# Focus_V7.net
KiCad netlist of a schematic drawn in EAGLE
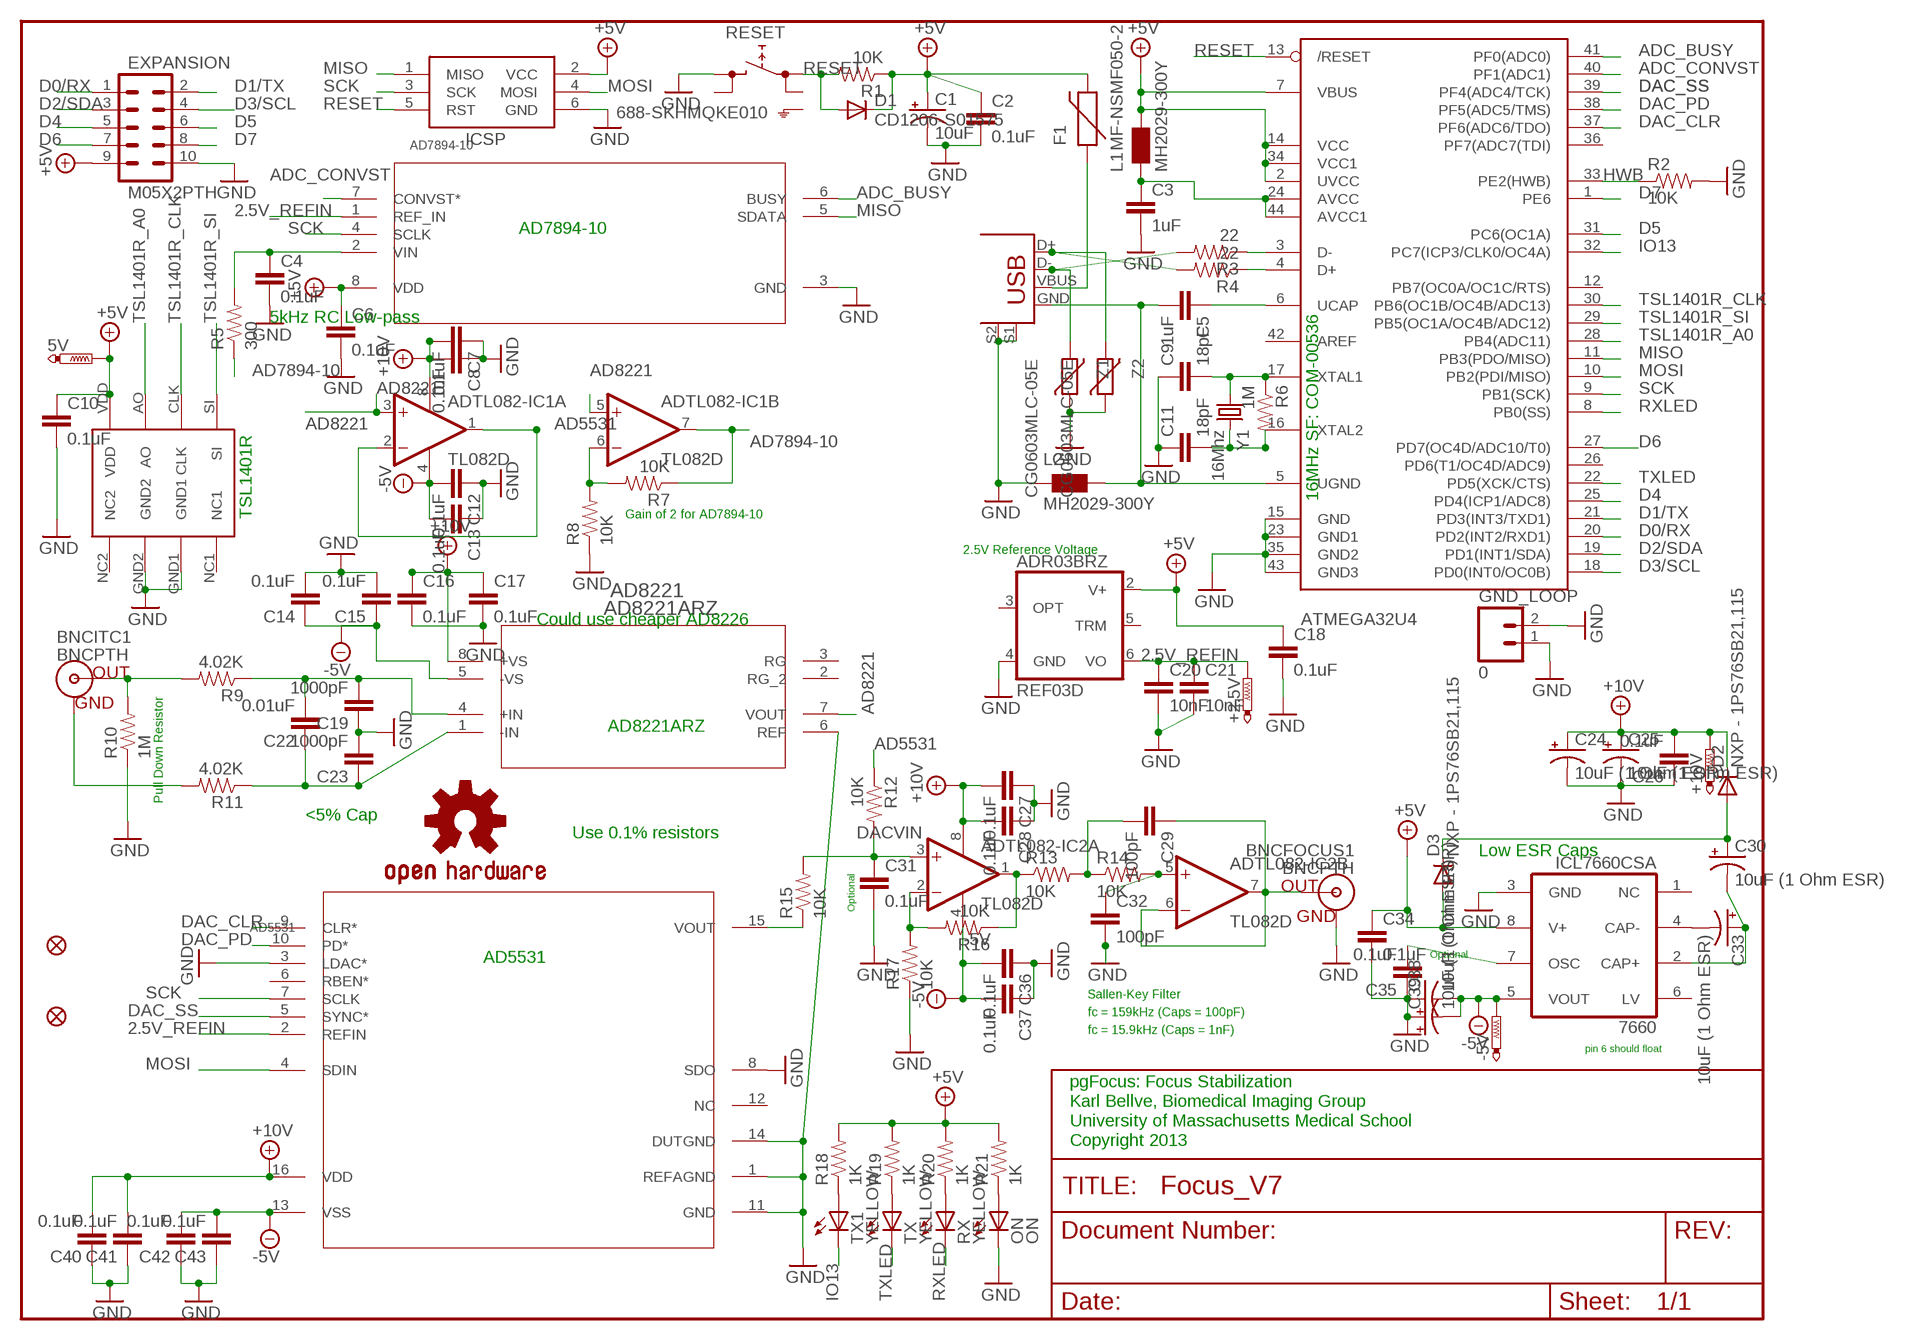
[diagram p0: schematic, sheet 1]

(export (version "E")
  (design (tool "Eeschema 10.0.6"))
  (components
    (comp (ref "+2.5V")
      (value "PTR1TP20R")
      (footprint "eagle-import:TP20R")
      (libsource (lib "eagle-import") (part "PTR1TP20R"))
    )
    (comp (ref "+10V")
      (value "PTR1TP20R")
      (footprint "eagle-import:TP20R")
      (libsource (lib "eagle-import") (part "PTR1TP20R"))
    )
    (comp (ref "-5V")
      (value "PTR1TP20R")
      (footprint "eagle-import:TP20R")
      (libsource (lib "eagle-import") (part "PTR1TP20R"))
    )
    (comp (ref "5V")
      (value "PTR1TP20R")
      (footprint "eagle-import:TP20R")
      (libsource (lib "eagle-import") (part "PTR1TP20R"))
    )
    (comp (ref "7660")
      (value "ICL7660CSA")
      (footprint "eagle-import:SO08")
      (fields (field (name "MF") "MAXIM"))
      (libsource (lib "eagle-import") (part "ICL7660CSA"))
    )
    (comp (ref "AD5531")
      (value "AD5531BRUZ")
      (footprint "eagle-import:RU_16")
      (libsource (lib "eagle-import") (part "AD5531BRUZ"))
    )
    (comp (ref "AD7894-10")
      (value "AD7894ARZ-10")
      (footprint "eagle-import:R_8")
      (fields (field (name "MANUFACTURER_PART_NUMBER") "AD7894ARZ-3"))
      (libsource (lib "eagle-import") (part "AD7894ARZ-3"))
    )
    (comp (ref "AD8221")
      (value "AD8221ARZ")
      (footprint "eagle-import:R_8")
      (libsource (lib "eagle-import") (part "AD8221ARZ"))
    )
    (comp (ref "ADR03BRZ")
      (value "REF03D")
      (footprint "eagle-import:SO08")
      (libsource (lib "eagle-import") (part "REF03D"))
    )
    (comp (ref "ADTL082-IC1")
      (value "TL082D")
      (footprint "eagle-import:SO08")
      (libsource (lib "eagle-import") (part "TL082D"))
    )
    (comp (ref "ADTL082-IC2")
      (value "TL082D")
      (footprint "eagle-import:SO08")
      (libsource (lib "eagle-import") (part "TL082D"))
    )
    (comp (ref "ATMEGA32U4")
      (value "ATMEGA32U4-AU")
      (footprint "eagle-import:TQFP44")
      (libsource (lib "eagle-import") (part "ATMEGA32U4-AU"))
    )
    (comp (ref "BNCFOCUS1")
      (value "BNCPTH")
      (footprint "eagle-import:BNC")
      (libsource (lib "eagle-import") (part "BNCPTH"))
    )
    (comp (ref "BNCITC1")
      (value "BNCPTH")
      (footprint "eagle-import:BNC")
      (libsource (lib "eagle-import") (part "BNCPTH"))
    )
    (comp (ref "C1")
      (value "10uF")
      (footprint "eagle-import:EIA3216-KIT")
      (libsource (lib "eagle-import") (part "CAP_POL1206-KIT"))
    )
    (comp (ref "C2")
      (value "0.1uF")
      (footprint "eagle-import:0603-CAP")
      (libsource (lib "eagle-import") (part "CAP0603-CAP"))
    )
    (comp (ref "C3")
      (value "1uF")
      (footprint "eagle-import:0603-CAP")
      (libsource (lib "eagle-import") (part "CAP0603-CAP"))
    )
    (comp (ref "C4")
      (value "0.1uF")
      (footprint "eagle-import:0603-CAP")
      (libsource (lib "eagle-import") (part "CAP0603-CAP"))
    )
    (comp (ref "C5")
      (value "1uF")
      (footprint "eagle-import:0603-CAP")
      (libsource (lib "eagle-import") (part "CAP0603-CAP"))
    )
    (comp (ref "C6")
      (value "0.1uF")
      (footprint "eagle-import:0603-CAP")
      (libsource (lib "eagle-import") (part "CAP0603-CAP"))
    )
    (comp (ref "C7")
      (value "0.1uF")
      (footprint "eagle-import:0603-CAP")
      (libsource (lib "eagle-import") (part "CAP0603-CAP"))
    )
    (comp (ref "C8")
      (value "0.1uF")
      (footprint "eagle-import:0603-CAP")
      (libsource (lib "eagle-import") (part "CAP0603-CAP"))
    )
    (comp (ref "C9")
      (value "18pF")
      (footprint "eagle-import:0603-CAP")
      (libsource (lib "eagle-import") (part "CAP0603-CAP"))
    )
    (comp (ref "C10")
      (value "0.1uF")
      (footprint "eagle-import:0603-CAP")
      (libsource (lib "eagle-import") (part "CAP0603-CAP"))
    )
    (comp (ref "C11")
      (value "18pF")
      (footprint "eagle-import:0603-CAP")
      (libsource (lib "eagle-import") (part "CAP0603-CAP"))
    )
    (comp (ref "C12")
      (value "0.1uF")
      (footprint "eagle-import:0603-CAP")
      (libsource (lib "eagle-import") (part "CAP0603-CAP"))
    )
    (comp (ref "C13")
      (value "0.1uF")
      (footprint "eagle-import:0603-CAP")
      (libsource (lib "eagle-import") (part "CAP0603-CAP"))
    )
    (comp (ref "C14")
      (value "0.1uF")
      (footprint "eagle-import:0603-CAP")
      (libsource (lib "eagle-import") (part "CAP0603-CAP"))
    )
    (comp (ref "C15")
      (value "0.1uF")
      (footprint "eagle-import:0603-CAP")
      (libsource (lib "eagle-import") (part "CAP0603-CAP"))
    )
    (comp (ref "C16")
      (value "0.1uF")
      (footprint "eagle-import:0603-CAP")
      (libsource (lib "eagle-import") (part "CAP0603-CAP"))
    )
    (comp (ref "C17")
      (value "0.1uF")
      (footprint "eagle-import:0603-CAP")
      (libsource (lib "eagle-import") (part "CAP0603-CAP"))
    )
    (comp (ref "C18")
      (value "0.1uF")
      (footprint "eagle-import:0603-CAP")
      (libsource (lib "eagle-import") (part "CAP0603-CAP"))
    )
    (comp (ref "C19")
      (value "1000pF")
      (footprint "eagle-import:0603-CAP")
      (libsource (lib "eagle-import") (part "CAP0603-CAP"))
    )
    (comp (ref "C20")
      (value "10nF")
      (footprint "eagle-import:0603-CAP")
      (libsource (lib "eagle-import") (part "CAP0603-CAP"))
    )
    (comp (ref "C21")
      (value "10nF")
      (footprint "eagle-import:0603-CAP")
      (libsource (lib "eagle-import") (part "CAP0603-CAP"))
    )
    (comp (ref "C22")
      (value "0.01uF")
      (footprint "eagle-import:0603-CAP")
      (libsource (lib "eagle-import") (part "CAP0603-CAP"))
    )
    (comp (ref "C23")
      (value "1000pF")
      (footprint "eagle-import:0603-CAP")
      (libsource (lib "eagle-import") (part "CAP0603-CAP"))
    )
    (comp (ref "C24")
      (value "10uF (1 Ohm ESR)")
      (footprint "eagle-import:EIA3216-KIT")
      (libsource (lib "eagle-import") (part "CAP_POL1206-KIT"))
    )
    (comp (ref "C25")
      (value "10uF (1 Ohm ESR)")
      (footprint "eagle-import:EIA3216-KIT")
      (libsource (lib "eagle-import") (part "CAP_POL1206-KIT"))
    )
    (comp (ref "C26")
      (value "0.1uF")
      (footprint "eagle-import:0603-CAP")
      (libsource (lib "eagle-import") (part "CAP0603-CAP"))
    )
    (comp (ref "C27")
      (value "0.1uF")
      (footprint "eagle-import:0603-CAP")
      (libsource (lib "eagle-import") (part "CAP0603-CAP"))
    )
    (comp (ref "C28")
      (value "0.1uF")
      (footprint "eagle-import:0603-CAP")
      (libsource (lib "eagle-import") (part "CAP0603-CAP"))
    )
    (comp (ref "C29")
      (value "100pF")
      (footprint "eagle-import:0603-CAP")
      (libsource (lib "eagle-import") (part "CAP0603-CAP"))
    )
    (comp (ref "C30")
      (value "10uF (1 Ohm ESR)")
      (footprint "eagle-import:EIA3216-KIT")
      (libsource (lib "eagle-import") (part "CAP_POL1206-KIT"))
    )
    (comp (ref "C31")
      (value "0.1uF")
      (footprint "eagle-import:0603-CAP")
      (libsource (lib "eagle-import") (part "CAP0603-CAP"))
    )
    (comp (ref "C32")
      (value "100pF")
      (footprint "eagle-import:0603-CAP")
      (libsource (lib "eagle-import") (part "CAP0603-CAP"))
    )
    (comp (ref "C33")
      (value "10uF (1 Ohm ESR)")
      (footprint "eagle-import:EIA3216-KIT")
      (libsource (lib "eagle-import") (part "CAP_POL1206-KIT"))
    )
    (comp (ref "C34")
      (value "0.1uF")
      (footprint "eagle-import:0603-CAP")
      (libsource (lib "eagle-import") (part "CAP0603-CAP"))
    )
    (comp (ref "C35")
      (value "0.1uF")
      (footprint "eagle-import:0603-CAP")
      (libsource (lib "eagle-import") (part "CAP0603-CAP"))
    )
    (comp (ref "C36")
      (value "0.1uF")
      (footprint "eagle-import:0603-CAP")
      (libsource (lib "eagle-import") (part "CAP0603-CAP"))
    )
    (comp (ref "C37")
      (value "0.1uF")
      (footprint "eagle-import:0603-CAP")
      (libsource (lib "eagle-import") (part "CAP0603-CAP"))
    )
    (comp (ref "C38")
      (value "10uF (1 Ohm ESR)")
      (footprint "eagle-import:EIA3216-KIT")
      (libsource (lib "eagle-import") (part "CAP_POL1206-KIT"))
    )
    (comp (ref "C39")
      (value "10uF (1 Ohm ESR)")
      (footprint "eagle-import:EIA3216-KIT")
      (libsource (lib "eagle-import") (part "CAP_POL1206-KIT"))
    )
    (comp (ref "C40")
      (value "0.1uF")
      (footprint "eagle-import:0603-CAP")
      (libsource (lib "eagle-import") (part "CAP0603-CAP"))
    )
    (comp (ref "C41")
      (value "0.1uF")
      (footprint "eagle-import:0603-CAP")
      (libsource (lib "eagle-import") (part "CAP0603-CAP"))
    )
    (comp (ref "C42")
      (value "0.1uF")
      (footprint "eagle-import:0603-CAP")
      (libsource (lib "eagle-import") (part "CAP0603-CAP"))
    )
    (comp (ref "C43")
      (value "0.1uF")
      (footprint "eagle-import:0603-CAP")
      (libsource (lib "eagle-import") (part "CAP0603-CAP"))
    )
    (comp (ref "D1")
      (value "CD1206-S01575")
      (footprint "eagle-import:MINIMELF")
      (libsource (lib "eagle-import") (part "DIODE-MINIMELF"))
    )
    (comp (ref "D2")
      (value "NXP - 1PS76SB21,115")
      (footprint "eagle-import:SOD-323")
      (libsource (lib "eagle-import") (part "DIODESOD"))
    )
    (comp (ref "D3")
      (value "NXP - 1PS76SB21,115")
      (footprint "eagle-import:SOD-323")
      (libsource (lib "eagle-import") (part "DIODESOD"))
    )
    (comp (ref "EXPANSION")
      (value "M05X2PTH")
      (footprint "eagle-import:AVR_ICSP")
      (libsource (lib "eagle-import") (part "M05X2PTH"))
    )
    (comp (ref "F1")
      (value "MF-NSMF050-2")
      (footprint "eagle-import:PTC-1206")
      (libsource (lib "eagle-import") (part "PTCSMD"))
    )
    (comp (ref "GND_LOOP")
      (value "0")
      (footprint "eagle-import:1X02")
      (libsource (lib "eagle-import") (part "M02NG"))
    )
    (comp (ref "ICSP")
      (value "AVRISP-6")
      (footprint "eagle-import:AVRISP")
      (libsource (lib "eagle-import") (part "AVRISP-6"))
    )
    (comp (ref "JP1")
      (value "FIDUCIAL1.5X3")
      (footprint "eagle-import:FIDUCIAL-1.5X3")
      (libsource (lib "eagle-import") (part "FIDUCIAL1.5X3"))
    )
    (comp (ref "JP2")
      (value "FIDUCIAL1.5X3")
      (footprint "eagle-import:FIDUCIAL-1.5X3")
      (libsource (lib "eagle-import") (part "FIDUCIAL1.5X3"))
    )
    (comp (ref "L1")
      (value "MH2029-300Y")
      (footprint "eagle-import:0805")
      (libsource (lib "eagle-import") (part "WE-CBF_0805"))
    )
    (comp (ref "L2")
      (value "MH2029-300Y")
      (footprint "eagle-import:0805")
      (libsource (lib "eagle-import") (part "WE-CBF_0805"))
    )
    (comp (ref "ON")
      (value "ON")
      (footprint "eagle-import:CHIPLED_0805")
      (libsource (lib "eagle-import") (part "LEDCHIPLED_0805"))
    )
    (comp (ref "R1")
      (value "10K")
      (footprint "eagle-import:0603-RES")
      (libsource (lib "eagle-import") (part "RESISTOR0603-RES"))
    )
    (comp (ref "R2")
      (value "10K")
      (footprint "eagle-import:0603-RES")
      (libsource (lib "eagle-import") (part "RESISTOR0603-RES"))
    )
    (comp (ref "R3")
      (value "22")
      (footprint "eagle-import:0603-RES")
      (libsource (lib "eagle-import") (part "RESISTOR0603-RES"))
    )
    (comp (ref "R4")
      (value "22")
      (footprint "eagle-import:0603-RES")
      (libsource (lib "eagle-import") (part "RESISTOR0603-RES"))
    )
    (comp (ref "R5")
      (value "300")
      (footprint "eagle-import:0603-RES")
      (libsource (lib "eagle-import") (part "RESISTOR0603-RES"))
    )
    (comp (ref "R6")
      (value "1M")
      (footprint "eagle-import:0603-RES")
      (libsource (lib "eagle-import") (part "RESISTOR0603-RES"))
    )
    (comp (ref "R7")
      (value "10K")
      (footprint "eagle-import:0603-RES")
      (libsource (lib "eagle-import") (part "RESISTOR0603-RES"))
    )
    (comp (ref "R8")
      (value "10K")
      (footprint "eagle-import:0603-RES")
      (libsource (lib "eagle-import") (part "RESISTOR0603-RES"))
    )
    (comp (ref "R9")
      (value "4.02K")
      (footprint "eagle-import:0603-RES")
      (libsource (lib "eagle-import") (part "RESISTOR0603-RES"))
    )
    (comp (ref "R10")
      (value "1M")
      (footprint "eagle-import:0603-RES")
      (libsource (lib "eagle-import") (part "RESISTOR0603-RES"))
    )
    (comp (ref "R11")
      (value "4.02K")
      (footprint "eagle-import:0603-RES")
      (libsource (lib "eagle-import") (part "RESISTOR0603-RES"))
    )
    (comp (ref "R12")
      (value "10K")
      (footprint "eagle-import:0603-RES")
      (libsource (lib "eagle-import") (part "RESISTOR0603-RES"))
    )
    (comp (ref "R13")
      (value "10K")
      (footprint "eagle-import:0603-RES")
      (libsource (lib "eagle-import") (part "RESISTOR0603-RES"))
    )
    (comp (ref "R14")
      (value "10K")
      (footprint "eagle-import:0603-RES")
      (libsource (lib "eagle-import") (part "RESISTOR0603-RES"))
    )
    (comp (ref "R15")
      (value "10K")
      (footprint "eagle-import:0603-RES")
      (libsource (lib "eagle-import") (part "RESISTOR0603-RES"))
    )
    (comp (ref "R16")
      (value "10K")
      (footprint "eagle-import:0603-RES")
      (libsource (lib "eagle-import") (part "RESISTOR0603-RES"))
    )
    (comp (ref "R17")
      (value "10K")
      (footprint "eagle-import:0603-RES")
      (libsource (lib "eagle-import") (part "RESISTOR0603-RES"))
    )
    (comp (ref "R18")
      (value "1K")
      (footprint "eagle-import:0603-RES")
      (libsource (lib "eagle-import") (part "RESISTOR0603-RES"))
    )
    (comp (ref "R19")
      (value "1K")
      (footprint "eagle-import:0603-RES")
      (libsource (lib "eagle-import") (part "RESISTOR0603-RES"))
    )
    (comp (ref "R20")
      (value "1K")
      (footprint "eagle-import:0603-RES")
      (libsource (lib "eagle-import") (part "RESISTOR0603-RES"))
    )
    (comp (ref "R21")
      (value "1K")
      (footprint "eagle-import:0603-RES")
      (libsource (lib "eagle-import") (part "RESISTOR0603-RES"))
    )
    (comp (ref "RESET")
      (value "688-SKHMQKE010")
      (footprint "eagle-import:SKHMPXE010")
      (libsource (lib "eagle-import") (part "SKHMPE010S"))
    )
    (comp (ref "RX")
      (value "YELLOW")
      (footprint "eagle-import:CHIPLED_0805")
      (libsource (lib "eagle-import") (part "LEDCHIPLED_0805"))
    )
    (comp (ref "TX")
      (value "YELLOW")
      (footprint "eagle-import:CHIPLED_0805")
      (libsource (lib "eagle-import") (part "LEDCHIPLED_0805"))
    )
    (comp (ref "TX1")
      (value "YELLOW")
      (footprint "eagle-import:CHIPLED_0805")
      (libsource (lib "eagle-import") (part "LEDCHIPLED_0805"))
    )
    (comp (ref "U$1")
      (value "TSL1401CL")
      (footprint "eagle-import:TSL1401CL")
      (libsource (lib "eagle-import") (part "TSL1401CL"))
    )
    (comp (ref "U$3")
      (value "OSHW-LOGOL")
      (footprint "eagle-import:OSHW-LOGO-L")
      (libsource (lib "eagle-import") (part "OSHW-LOGOL"))
    )
    (comp (ref "X1")
      (value "USB+SHIELD")
      (footprint "eagle-import:USB-B-PTH")
      (libsource (lib "eagle-import") (part "USB+SHIELD"))
    )
    (comp (ref "Y1")
      (value "16Mhz")
      (footprint "eagle-import:HC49U-V")
      (libsource (lib "eagle-import") (part "CRYSTALHC49UV"))
    )
    (comp (ref "Z1")
      (value "CG0603MLC-05E")
      (footprint "eagle-import:CT_CN0603")
      (libsource (lib "eagle-import") (part "VARISTORCN0603"))
    )
    (comp (ref "Z2")
      (value "CG0603MLC-05E")
      (footprint "eagle-import:CT_CN0603")
      (libsource (lib "eagle-import") (part "VARISTORCN0603"))
    )
  )
  (nets
    (net (code "1") (name "+5V") (class "Default")
      (node (ref "5V") (pin "TP") (pinfunction "TP_TP") (pintype "input"))
      (node (ref "7660") (pin "8") (pinfunction "V+_8") (pintype "power_in"))
      (node (ref "AD7894-10") (pin "8") (pinfunction "VDD_8") (pintype "power_in"))
      (node (ref "ADR03BRZ") (pin "2") (pinfunction "V+_2") (pintype "power_in"))
      (node (ref "ATMEGA32U4") (pin "14") (pinfunction "VCC_14") (pintype "bidirectional"))
      (node (ref "ATMEGA32U4") (pin "2") (pinfunction "UVCC_2") (pintype "bidirectional"))
      (node (ref "ATMEGA32U4") (pin "34") (pinfunction "VCC1_34") (pintype "bidirectional"))
      (node (ref "ATMEGA32U4") (pin "7") (pinfunction "VBUS_7") (pintype "bidirectional"))
      (node (ref "C1") (pin "A") (pinfunction "+_A") (pintype "passive"))
      (node (ref "C10") (pin "1") (pinfunction "1_1") (pintype "passive"))
      (node (ref "C18") (pin "1") (pinfunction "1_1") (pintype "passive"))
      (node (ref "C2") (pin "1") (pinfunction "1_1") (pintype "passive"))
      (node (ref "C34") (pin "1") (pinfunction "1_1") (pintype "passive"))
      (node (ref "C6") (pin "1") (pinfunction "1_1") (pintype "passive"))
      (node (ref "D1") (pin "C") (pinfunction "C_C") (pintype "passive"))
      (node (ref "D3") (pin "2") (pinfunction "A_2") (pintype "passive"))
      (node (ref "EXPANSION") (pin "9") (pinfunction "9_9") (pintype "passive"))
      (node (ref "F1") (pin "2") (pinfunction "2_2") (pintype "bidirectional"))
      (node (ref "ICSP") (pin "2") (pinfunction "VCC_2") (pintype "power_in"))
      (node (ref "L1") (pin "2") (pinfunction "2_2") (pintype "passive"))
      (node (ref "R1") (pin "1") (pinfunction "1_1") (pintype "passive"))
      (node (ref "R18") (pin "2") (pinfunction "2_2") (pintype "passive"))
      (node (ref "R19") (pin "2") (pinfunction "2_2") (pintype "passive"))
      (node (ref "R20") (pin "2") (pinfunction "2_2") (pintype "passive"))
      (node (ref "R21") (pin "2") (pinfunction "2_2") (pintype "passive"))
      (node (ref "U$1") (pin "VDD") (pinfunction "VDD_VDD") (pintype "bidirectional"))
    )
    (net (code "2") (name "+10V") (class "Default")
      (node (ref "+10V") (pin "TP") (pinfunction "TP_TP") (pintype "input"))
      (node (ref "AD5531") (pin "16") (pinfunction "VDD_16") (pintype "power_in"))
      (node (ref "AD8221") (pin "8") (pinfunction "+VS_8") (pintype "power_in"))
      (node (ref "ADTL082-IC1") (pin "8") (pinfunction "V+_8") (pintype "power_in"))
      (node (ref "ADTL082-IC2") (pin "8") (pinfunction "V+_8") (pintype "power_in"))
      (node (ref "C16") (pin "1") (pinfunction "1_1") (pintype "passive"))
      (node (ref "C17") (pin "1") (pinfunction "1_1") (pintype "passive"))
      (node (ref "C24") (pin "A") (pinfunction "+_A") (pintype "passive"))
      (node (ref "C25") (pin "A") (pinfunction "+_A") (pintype "passive"))
      (node (ref "C26") (pin "2") (pinfunction "2_2") (pintype "passive"))
      (node (ref "C27") (pin "2") (pinfunction "2_2") (pintype "passive"))
      (node (ref "C28") (pin "2") (pinfunction "2_2") (pintype "passive"))
      (node (ref "C40") (pin "2") (pinfunction "2_2") (pintype "passive"))
      (node (ref "C41") (pin "2") (pinfunction "2_2") (pintype "passive"))
      (node (ref "C7") (pin "2") (pinfunction "2_2") (pintype "passive"))
      (node (ref "C8") (pin "2") (pinfunction "2_2") (pintype "passive"))
      (node (ref "D2") (pin "1") (pinfunction "C_1") (pintype "passive"))
    )
    (net (code "3") (name "-5V") (class "Default")
      (node (ref "-5V") (pin "TP") (pinfunction "TP_TP") (pintype "input"))
      (node (ref "7660") (pin "5") (pinfunction "VOUT_5") (pintype "output"))
      (node (ref "AD5531") (pin "13") (pinfunction "VSS_13") (pintype "power_in"))
      (node (ref "AD8221") (pin "5") (pinfunction "-VS_5") (pintype "power_in"))
      (node (ref "ADTL082-IC1") (pin "4") (pinfunction "V-_4") (pintype "power_in"))
      (node (ref "ADTL082-IC2") (pin "4") (pinfunction "V-_4") (pintype "power_in"))
      (node (ref "C12") (pin "2") (pinfunction "2_2") (pintype "passive"))
      (node (ref "C13") (pin "2") (pinfunction "2_2") (pintype "passive"))
      (node (ref "C14") (pin "1") (pinfunction "1_1") (pintype "passive"))
      (node (ref "C15") (pin "1") (pinfunction "1_1") (pintype "passive"))
      (node (ref "C36") (pin "2") (pinfunction "2_2") (pintype "passive"))
      (node (ref "C37") (pin "2") (pinfunction "2_2") (pintype "passive"))
      (node (ref "C38") (pin "C") (pinfunction "-_C") (pintype "passive"))
      (node (ref "C39") (pin "C") (pinfunction "-_C") (pintype "passive"))
      (node (ref "C42") (pin "2") (pinfunction "2_2") (pintype "passive"))
      (node (ref "C43") (pin "2") (pinfunction "2_2") (pintype "passive"))
    )
    (net (code "4") (name "/2.5V_REFIN") (class "Default")
      (node (ref "+2.5V") (pin "TP") (pinfunction "TP_TP") (pintype "input"))
      (node (ref "AD5531") (pin "2") (pinfunction "REFIN_2") (pintype "passive"))
      (node (ref "AD7894-10") (pin "1") (pinfunction "REF_IN_1") (pintype "passive"))
      (node (ref "ADR03BRZ") (pin "6") (pinfunction "VO_6") (pintype "output"))
      (node (ref "C20") (pin "1") (pinfunction "1_1") (pintype "passive"))
      (node (ref "C21") (pin "1") (pinfunction "1_1") (pintype "passive"))
    )
    (net (code "5") (name "/AD5531") (class "Default")
      (node (ref "ADTL082-IC1") (pin "1") (pinfunction "OUT_1") (pintype "output"))
      (node (ref "ADTL082-IC1") (pin "2") (pinfunction "-IN_2") (pintype "input"))
      (node (ref "R12") (pin "1") (pinfunction "1_1") (pintype "passive"))
    )
    (net (code "6") (name "/AD7894-10") (class "Default")
      (node (ref "ADTL082-IC1") (pin "7") (pinfunction "OUT_7") (pintype "output"))
      (node (ref "R5") (pin "1") (pinfunction "1_1") (pintype "passive"))
      (node (ref "R7") (pin "1") (pinfunction "1_1") (pintype "passive"))
    )
    (net (code "7") (name "/AD8221") (class "Default")
      (node (ref "AD8221") (pin "7") (pinfunction "VOUT_7") (pintype "output"))
      (node (ref "ADTL082-IC1") (pin "3") (pinfunction "+IN_3") (pintype "input"))
      (node (ref "ADTL082-IC1") (pin "5") (pinfunction "+IN_5") (pintype "input"))
    )
    (net (code "8") (name "/ADC_BUSY") (class "Default")
      (node (ref "AD7894-10") (pin "6") (pinfunction "BUSY_6") (pintype "passive"))
      (node (ref "ATMEGA32U4") (pin "41") (pinfunction "PF0(ADC0)_41") (pintype "bidirectional"))
    )
    (net (code "9") (name "/ADC_CONVST") (class "Default")
      (node (ref "AD7894-10") (pin "7") (pinfunction "CONVST*_7") (pintype "passive"))
      (node (ref "ATMEGA32U4") (pin "40") (pinfunction "PF1(ADC1)_40") (pintype "bidirectional"))
    )
    (net (code "10") (name "/D0{slash}RX") (class "Default")
      (node (ref "ATMEGA32U4") (pin "20") (pinfunction "PD2(INT2/RXD1)_20") (pintype "bidirectional"))
      (node (ref "EXPANSION") (pin "1") (pinfunction "1_1") (pintype "passive"))
    )
    (net (code "11") (name "/D1{slash}TX") (class "Default")
      (node (ref "ATMEGA32U4") (pin "21") (pinfunction "PD3(INT3/TXD1)_21") (pintype "bidirectional"))
      (node (ref "EXPANSION") (pin "2") (pinfunction "2_2") (pintype "passive"))
    )
    (net (code "12") (name "/D2{slash}SDA") (class "Default")
      (node (ref "ATMEGA32U4") (pin "19") (pinfunction "PD1(INT1/SDA)_19") (pintype "bidirectional"))
      (node (ref "EXPANSION") (pin "3") (pinfunction "3_3") (pintype "passive"))
    )
    (net (code "13") (name "/D3{slash}SCL") (class "Default")
      (node (ref "ATMEGA32U4") (pin "18") (pinfunction "PD0(INT0/OC0B)_18") (pintype "bidirectional"))
      (node (ref "EXPANSION") (pin "4") (pinfunction "4_4") (pintype "passive"))
    )
    (net (code "14") (name "/D4") (class "Default")
      (node (ref "ATMEGA32U4") (pin "25") (pinfunction "PD4(ICP1/ADC8)_25") (pintype "bidirectional"))
      (node (ref "EXPANSION") (pin "5") (pinfunction "5_5") (pintype "passive"))
    )
    (net (code "15") (name "/D5") (class "Default")
      (node (ref "ATMEGA32U4") (pin "31") (pinfunction "PC6(OC1A)_31") (pintype "bidirectional"))
      (node (ref "EXPANSION") (pin "6") (pinfunction "6_6") (pintype "passive"))
    )
    (net (code "16") (name "/D6") (class "Default")
      (node (ref "ATMEGA32U4") (pin "27") (pinfunction "PD7(OC4D/ADC10/T0)_27") (pintype "bidirectional"))
      (node (ref "EXPANSION") (pin "7") (pinfunction "7_7") (pintype "passive"))
    )
    (net (code "17") (name "/D7") (class "Default")
      (node (ref "ATMEGA32U4") (pin "1") (pinfunction "PE6_1") (pintype "bidirectional"))
      (node (ref "EXPANSION") (pin "8") (pinfunction "8_8") (pintype "passive"))
    )
    (net (code "18") (name "/DACVIN") (class "Default")
      (node (ref "ADTL082-IC2") (pin "3") (pinfunction "+IN_3") (pintype "input"))
      (node (ref "C31") (pin "1") (pinfunction "1_1") (pintype "passive"))
      (node (ref "R12") (pin "2") (pinfunction "2_2") (pintype "passive"))
      (node (ref "R15") (pin "2") (pinfunction "2_2") (pintype "passive"))
    )
    (net (code "19") (name "/DAC_CLR") (class "Default")
      (node (ref "AD5531") (pin "9") (pinfunction "CLR*_9") (pintype "passive"))
      (node (ref "ATMEGA32U4") (pin "37") (pinfunction "PF6(ADC6/TDO)_37") (pintype "bidirectional"))
    )
    (net (code "20") (name "/DAC_PD") (class "Default")
      (node (ref "AD5531") (pin "10") (pinfunction "PD*_10") (pintype "passive"))
      (node (ref "ATMEGA32U4") (pin "38") (pinfunction "PF5(ADC5/TMS)_38") (pintype "bidirectional"))
    )
    (net (code "21") (name "/DAC_SS") (class "Default")
      (node (ref "AD5531") (pin "5") (pinfunction "SYNC*_5") (pintype "passive"))
      (node (ref "ATMEGA32U4") (pin "39") (pinfunction "PF4(ADC4/TCK)_39") (pintype "bidirectional"))
    )
    (net (code "22") (name "/HWB") (class "Default")
      (node (ref "ATMEGA32U4") (pin "33") (pinfunction "PE2(HWB)_33") (pintype "bidirectional"))
      (node (ref "R2") (pin "1") (pinfunction "1_1") (pintype "passive"))
    )
    (net (code "23") (name "/IO13") (class "Default")
      (node (ref "ATMEGA32U4") (pin "32") (pinfunction "PC7(ICP3/CLK0/OC4A)_32") (pintype "bidirectional"))
      (node (ref "TX1") (pin "CATHODE") (pinfunction "C_CATHODE") (pintype "passive"))
    )
    (net (code "24") (name "/MISO") (class "Default")
      (node (ref "AD7894-10") (pin "5") (pinfunction "SDATA_5") (pintype "passive"))
      (node (ref "ATMEGA32U4") (pin "11") (pinfunction "PB3(PDO/MISO)_11") (pintype "bidirectional"))
      (node (ref "ICSP") (pin "1") (pinfunction "MISO_1") (pintype "input"))
    )
    (net (code "25") (name "/MOSI") (class "Default")
      (node (ref "AD5531") (pin "4") (pinfunction "SDIN_4") (pintype "passive"))
      (node (ref "ATMEGA32U4") (pin "10") (pinfunction "PB2(PDI/MISO)_10") (pintype "bidirectional"))
      (node (ref "ICSP") (pin "4") (pinfunction "MOSI_4") (pintype "output"))
    )
    (net (code "26") (name "/RESET") (class "Default")
      (node (ref "ATMEGA32U4") (pin "13") (pinfunction "/RESET_13") (pintype "bidirectional"))
      (node (ref "D1") (pin "A") (pinfunction "A_A") (pintype "passive"))
      (node (ref "ICSP") (pin "5") (pinfunction "RST_5") (pintype "output"))
      (node (ref "R1") (pin "2") (pinfunction "2_2") (pintype "passive"))
      (node (ref "RESET") (pin "1") (pinfunction "1.1_1") (pintype "passive"))
    )
    (net (code "27") (name "/RXLED") (class "Default")
      (node (ref "ATMEGA32U4") (pin "8") (pinfunction "PB0(SS)_8") (pintype "bidirectional"))
      (node (ref "RX") (pin "CATHODE") (pinfunction "C_CATHODE") (pintype "passive"))
    )
    (net (code "28") (name "/SCK") (class "Default")
      (node (ref "AD5531") (pin "7") (pinfunction "SCLK_7") (pintype "passive"))
      (node (ref "AD7894-10") (pin "4") (pinfunction "SCLK_4") (pintype "passive"))
      (node (ref "ATMEGA32U4") (pin "9") (pinfunction "PB1(SCK)_9") (pintype "bidirectional"))
      (node (ref "ICSP") (pin "3") (pinfunction "SCK_3") (pintype "output"))
    )
    (net (code "29") (name "/TSL1401R_A0") (class "Default")
      (node (ref "ATMEGA32U4") (pin "28") (pinfunction "PB4(ADC11)_28") (pintype "bidirectional"))
      (node (ref "U$1") (pin "AO") (pinfunction "AO_AO") (pintype "bidirectional"))
    )
    (net (code "30") (name "/TSL1401R_CLK") (class "Default")
      (node (ref "ATMEGA32U4") (pin "30") (pinfunction "PB6(OC1B/OC4B/ADC13)_30") (pintype "bidirectional"))
      (node (ref "U$1") (pin "CLK") (pinfunction "CLK_CLK") (pintype "bidirectional"))
    )
    (net (code "31") (name "/TSL1401R_SI") (class "Default")
      (node (ref "ATMEGA32U4") (pin "29") (pinfunction "PB5(OC1A/OC4B/ADC12)_29") (pintype "bidirectional"))
      (node (ref "U$1") (pin "SI") (pinfunction "SI_SI") (pintype "bidirectional"))
    )
    (net (code "32") (name "/TXLED") (class "Default")
      (node (ref "ATMEGA32U4") (pin "22") (pinfunction "PD5(XCK/CTS)_22") (pintype "bidirectional"))
      (node (ref "TX") (pin "CATHODE") (pinfunction "C_CATHODE") (pintype "passive"))
    )
    (net (code "33") (name "GND") (class "Default")
      (node (ref "7660") (pin "3") (pinfunction "GND_3") (pintype "power_in"))
      (node (ref "AD5531") (pin "1") (pinfunction "REFAGND_1") (pintype "passive"))
      (node (ref "AD5531") (pin "11") (pinfunction "GND_11") (pintype "passive"))
      (node (ref "AD5531") (pin "14") (pinfunction "DUTGND_14") (pintype "passive"))
      (node (ref "AD5531") (pin "3") (pinfunction "LDAC*_3") (pintype "passive"))
      (node (ref "AD5531") (pin "8") (pinfunction "SDO_8") (pintype "passive"))
      (node (ref "AD7894-10") (pin "3") (pinfunction "GND_3") (pintype "passive"))
      (node (ref "AD8221") (pin "6") (pinfunction "REF_6") (pintype "output"))
      (node (ref "ADR03BRZ") (pin "4") (pinfunction "GND_4") (pintype "power_in"))
      (node (ref "ATMEGA32U4") (pin "15") (pinfunction "GND_15") (pintype "bidirectional"))
      (node (ref "ATMEGA32U4") (pin "23") (pinfunction "GND1_23") (pintype "bidirectional"))
      (node (ref "ATMEGA32U4") (pin "35") (pinfunction "GND2_35") (pintype "bidirectional"))
      (node (ref "ATMEGA32U4") (pin "43") (pinfunction "GND3_43") (pintype "bidirectional"))
      (node (ref "BNCFOCUS1") (pin "GND") (pinfunction "GND_GND") (pintype "bidirectional"))
      (node (ref "C1") (pin "C") (pinfunction "-_C") (pintype "passive"))
      (node (ref "C10") (pin "2") (pinfunction "2_2") (pintype "passive"))
      (node (ref "C11") (pin "1") (pinfunction "1_1") (pintype "passive"))
      (node (ref "C12") (pin "1") (pinfunction "1_1") (pintype "passive"))
      (node (ref "C13") (pin "1") (pinfunction "1_1") (pintype "passive"))
      (node (ref "C14") (pin "2") (pinfunction "2_2") (pintype "passive"))
      (node (ref "C15") (pin "2") (pinfunction "2_2") (pintype "passive"))
      (node (ref "C16") (pin "2") (pinfunction "2_2") (pintype "passive"))
      (node (ref "C17") (pin "2") (pinfunction "2_2") (pintype "passive"))
      (node (ref "C18") (pin "2") (pinfunction "2_2") (pintype "passive"))
      (node (ref "C19") (pin "1") (pinfunction "1_1") (pintype "passive"))
      (node (ref "C2") (pin "2") (pinfunction "2_2") (pintype "passive"))
      (node (ref "C20") (pin "2") (pinfunction "2_2") (pintype "passive"))
      (node (ref "C21") (pin "2") (pinfunction "2_2") (pintype "passive"))
      (node (ref "C23") (pin "2") (pinfunction "2_2") (pintype "passive"))
      (node (ref "C24") (pin "C") (pinfunction "-_C") (pintype "passive"))
      (node (ref "C25") (pin "C") (pinfunction "-_C") (pintype "passive"))
      (node (ref "C26") (pin "1") (pinfunction "1_1") (pintype "passive"))
      (node (ref "C27") (pin "1") (pinfunction "1_1") (pintype "passive"))
      (node (ref "C28") (pin "1") (pinfunction "1_1") (pintype "passive"))
      (node (ref "C3") (pin "2") (pinfunction "2_2") (pintype "passive"))
      (node (ref "C31") (pin "2") (pinfunction "2_2") (pintype "passive"))
      (node (ref "C32") (pin "2") (pinfunction "2_2") (pintype "passive"))
      (node (ref "C34") (pin "2") (pinfunction "2_2") (pintype "passive"))
      (node (ref "C35") (pin "1") (pinfunction "1_1") (pintype "passive"))
      (node (ref "C36") (pin "1") (pinfunction "1_1") (pintype "passive"))
      (node (ref "C37") (pin "1") (pinfunction "1_1") (pintype "passive"))
      (node (ref "C38") (pin "A") (pinfunction "+_A") (pintype "passive"))
      (node (ref "C39") (pin "A") (pinfunction "+_A") (pintype "passive"))
      (node (ref "C4") (pin "2") (pinfunction "2_2") (pintype "passive"))
      (node (ref "C40") (pin "1") (pinfunction "1_1") (pintype "passive"))
      (node (ref "C41") (pin "1") (pinfunction "1_1") (pintype "passive"))
      (node (ref "C42") (pin "1") (pinfunction "1_1") (pintype "passive"))
      (node (ref "C43") (pin "1") (pinfunction "1_1") (pintype "passive"))
      (node (ref "C6") (pin "2") (pinfunction "2_2") (pintype "passive"))
      (node (ref "C7") (pin "1") (pinfunction "1_1") (pintype "passive"))
      (node (ref "C8") (pin "1") (pinfunction "1_1") (pintype "passive"))
      (node (ref "C9") (pin "1") (pinfunction "1_1") (pintype "passive"))
      (node (ref "EXPANSION") (pin "10") (pinfunction "10_10") (pintype "passive"))
      (node (ref "GND_LOOP") (pin "1") (pinfunction "1_1") (pintype "passive"))
      (node (ref "GND_LOOP") (pin "2") (pinfunction "2_2") (pintype "passive"))
      (node (ref "ICSP") (pin "6") (pinfunction "GND_6") (pintype "power_in"))
      (node (ref "L2") (pin "1") (pinfunction "1_1") (pintype "passive"))
      (node (ref "ON") (pin "CATHODE") (pinfunction "C_CATHODE") (pintype "passive"))
      (node (ref "R10") (pin "1") (pinfunction "1_1") (pintype "passive"))
      (node (ref "R17") (pin "1") (pinfunction "1_1") (pintype "passive"))
      (node (ref "R2") (pin "2") (pinfunction "2_2") (pintype "passive"))
      (node (ref "R8") (pin "1") (pinfunction "1_1") (pintype "passive"))
      (node (ref "RESET") (pin "3") (pinfunction "2.1_3") (pintype "passive"))
      (node (ref "U$1") (pin "GND1") (pinfunction "GND1_GND1") (pintype "bidirectional"))
      (node (ref "U$1") (pin "GND2") (pinfunction "GND2_GND2") (pintype "bidirectional"))
      (node (ref "X1") (pin "S1") (pinfunction "P$1_S1") (pintype "bidirectional"))
      (node (ref "X1") (pin "S2") (pinfunction "P$2_S2") (pintype "bidirectional"))
      (node (ref "Z1") (pin "1") (pinfunction "1_1") (pintype "passive"))
      (node (ref "Z2") (pin "1") (pinfunction "1_1") (pintype "passive"))
    )
    (net (code "34") (name "Net-(7660-CAP+)") (class "Default")
      (node (ref "7660") (pin "2") (pinfunction "CAP+_2") (pintype "passive"))
      (node (ref "C30") (pin "C") (pinfunction "-_C") (pintype "passive"))
      (node (ref "C33") (pin "A") (pinfunction "+_A") (pintype "passive"))
    )
    (net (code "35") (name "Net-(7660-CAP-)") (class "Default")
      (node (ref "7660") (pin "4") (pinfunction "CAP-_4") (pintype "passive"))
      (node (ref "C33") (pin "C") (pinfunction "-_C") (pintype "passive"))
    )
    (net (code "36") (name "Net-(7660-OSC)") (class "Default")
      (node (ref "7660") (pin "7") (pinfunction "OSC_7") (pintype "output"))
      (node (ref "C35") (pin "2") (pinfunction "2_2") (pintype "passive"))
    )
    (net (code "37") (name "Net-(AD5531-VOUT)") (class "Default")
      (node (ref "AD5531") (pin "15") (pinfunction "VOUT_15") (pintype "passive"))
      (node (ref "R15") (pin "1") (pinfunction "1_1") (pintype "passive"))
    )
    (net (code "38") (name "Net-(AD7894-10-VIN)") (class "Default")
      (node (ref "AD7894-10") (pin "2") (pinfunction "VIN_2") (pintype "passive"))
      (node (ref "C4") (pin "1") (pinfunction "1_1") (pintype "passive"))
      (node (ref "R5") (pin "2") (pinfunction "2_2") (pintype "passive"))
    )
    (net (code "39") (name "Net-(AD8221-+IN)") (class "Default")
      (node (ref "AD8221") (pin "4") (pinfunction "+IN_4") (pintype "input"))
      (node (ref "C19") (pin "2") (pinfunction "2_2") (pintype "passive"))
      (node (ref "C22") (pin "2") (pinfunction "2_2") (pintype "passive"))
      (node (ref "R9") (pin "1") (pinfunction "1_1") (pintype "passive"))
    )
    (net (code "40") (name "Net-(AD8221--IN)") (class "Default")
      (node (ref "AD8221") (pin "1") (pinfunction "-IN_1") (pintype "input"))
      (node (ref "C22") (pin "1") (pinfunction "1_1") (pintype "passive"))
      (node (ref "C23") (pin "1") (pinfunction "1_1") (pintype "passive"))
      (node (ref "R11") (pin "1") (pinfunction "1_1") (pintype "passive"))
    )
    (net (code "41") (name "Net-(ADTL082-IC1B--IN)") (class "Default")
      (node (ref "ADTL082-IC1") (pin "6") (pinfunction "-IN_6") (pintype "input"))
      (node (ref "R7") (pin "2") (pinfunction "2_2") (pintype "passive"))
      (node (ref "R8") (pin "2") (pinfunction "2_2") (pintype "passive"))
    )
    (net (code "42") (name "Net-(ADTL082-IC2A--IN)") (class "Default")
      (node (ref "ADTL082-IC2") (pin "2") (pinfunction "-IN_2") (pintype "input"))
      (node (ref "R16") (pin "2") (pinfunction "2_2") (pintype "passive"))
      (node (ref "R17") (pin "2") (pinfunction "2_2") (pintype "passive"))
    )
    (net (code "43") (name "Net-(ADTL082-IC2A-OUT)") (class "Default")
      (node (ref "ADTL082-IC2") (pin "1") (pinfunction "OUT_1") (pintype "output"))
      (node (ref "R13") (pin "1") (pinfunction "1_1") (pintype "passive"))
      (node (ref "R16") (pin "1") (pinfunction "1_1") (pintype "passive"))
    )
    (net (code "44") (name "Net-(ADTL082-IC2B-+IN)") (class "Default")
      (node (ref "ADTL082-IC2") (pin "5") (pinfunction "+IN_5") (pintype "input"))
      (node (ref "C32") (pin "1") (pinfunction "1_1") (pintype "passive"))
      (node (ref "R14") (pin "2") (pinfunction "2_2") (pintype "passive"))
    )
    (net (code "45") (name "Net-(ADTL082-IC2B--IN)") (class "Default")
      (node (ref "ADTL082-IC2") (pin "6") (pinfunction "-IN_6") (pintype "input"))
      (node (ref "ADTL082-IC2") (pin "7") (pinfunction "OUT_7") (pintype "output"))
      (node (ref "BNCFOCUS1") (pin "S") (pinfunction "OUT_S") (pintype "bidirectional"))
      (node (ref "C29") (pin "1") (pinfunction "1_1") (pintype "passive"))
    )
    (net (code "46") (name "Net-(ATMEGA32U4-AVCC)") (class "Default")
      (node (ref "ATMEGA32U4") (pin "24") (pinfunction "AVCC_24") (pintype "bidirectional"))
      (node (ref "ATMEGA32U4") (pin "44") (pinfunction "AVCC1_44") (pintype "bidirectional"))
      (node (ref "C3") (pin "1") (pinfunction "1_1") (pintype "passive"))
      (node (ref "L1") (pin "1") (pinfunction "1_1") (pintype "passive"))
    )
    (net (code "47") (name "Net-(ATMEGA32U4-D+)") (class "Default")
      (node (ref "ATMEGA32U4") (pin "4") (pinfunction "D+_4") (pintype "bidirectional"))
      (node (ref "R4") (pin "1") (pinfunction "1_1") (pintype "passive"))
    )
    (net (code "48") (name "Net-(ATMEGA32U4-D-)") (class "Default")
      (node (ref "ATMEGA32U4") (pin "3") (pinfunction "D-_3") (pintype "bidirectional"))
      (node (ref "R3") (pin "1") (pinfunction "1_1") (pintype "passive"))
    )
    (net (code "49") (name "Net-(ATMEGA32U4-UCAP)") (class "Default")
      (node (ref "ATMEGA32U4") (pin "6") (pinfunction "UCAP_6") (pintype "bidirectional"))
      (node (ref "C5") (pin "1") (pinfunction "1_1") (pintype "passive"))
    )
    (net (code "50") (name "Net-(ATMEGA32U4-UGND)") (class "Default")
      (node (ref "ATMEGA32U4") (pin "5") (pinfunction "UGND_5") (pintype "bidirectional"))
      (node (ref "C5") (pin "2") (pinfunction "2_2") (pintype "passive"))
      (node (ref "L2") (pin "2") (pinfunction "2_2") (pintype "passive"))
      (node (ref "X1") (pin "GND") (pinfunction "GND_GND") (pintype "bidirectional"))
    )
    (net (code "51") (name "Net-(ATMEGA32U4-XTAL1)") (class "Default")
      (node (ref "ATMEGA32U4") (pin "17") (pinfunction "XTAL1_17") (pintype "bidirectional"))
      (node (ref "C9") (pin "2") (pinfunction "2_2") (pintype "passive"))
      (node (ref "R6") (pin "1") (pinfunction "1_1") (pintype "passive"))
      (node (ref "Y1") (pin "1") (pinfunction "1_1") (pintype "passive"))
    )
    (net (code "52") (name "Net-(ATMEGA32U4-XTAL2)") (class "Default")
      (node (ref "ATMEGA32U4") (pin "16") (pinfunction "XTAL2_16") (pintype "bidirectional"))
      (node (ref "C11") (pin "2") (pinfunction "2_2") (pintype "passive"))
      (node (ref "R6") (pin "2") (pinfunction "2_2") (pintype "passive"))
      (node (ref "Y1") (pin "2") (pinfunction "2_2") (pintype "passive"))
    )
    (net (code "53") (name "Net-(BNCITC1-OUT)") (class "Default")
      (node (ref "BNCITC1") (pin "S") (pinfunction "OUT_S") (pintype "bidirectional"))
      (node (ref "R10") (pin "2") (pinfunction "2_2") (pintype "passive"))
      (node (ref "R9") (pin "2") (pinfunction "2_2") (pintype "passive"))
    )
    (net (code "54") (name "Net-(BNCITC1-PadGND)") (class "Default")
      (node (ref "BNCITC1") (pin "GND") (pinfunction "GND_GND") (pintype "bidirectional"))
      (node (ref "R11") (pin "2") (pinfunction "2_2") (pintype "passive"))
    )
    (net (code "55") (name "Net-(C29-Pad2)") (class "Default")
      (node (ref "C29") (pin "2") (pinfunction "2_2") (pintype "passive"))
      (node (ref "R13") (pin "2") (pinfunction "2_2") (pintype "passive"))
      (node (ref "R14") (pin "1") (pinfunction "1_1") (pintype "passive"))
    )
    (net (code "56") (name "Net-(C30-+)") (class "Default")
      (node (ref "C30") (pin "A") (pinfunction "+_A") (pintype "passive"))
      (node (ref "D2") (pin "2") (pinfunction "A_2") (pintype "passive"))
      (node (ref "D3") (pin "1") (pinfunction "C_1") (pintype "passive"))
    )
    (net (code "57") (name "Net-(F1-Pad1)") (class "Default")
      (node (ref "F1") (pin "1") (pinfunction "1_1") (pintype "bidirectional"))
      (node (ref "X1") (pin "VBUS") (pinfunction "VBUS_VBUS") (pintype "bidirectional"))
    )
    (net (code "58") (name "Net-(ON-A)") (class "Default")
      (node (ref "ON") (pin "ANODE") (pinfunction "A_ANODE") (pintype "passive"))
      (node (ref "R21") (pin "1") (pinfunction "1_1") (pintype "passive"))
    )
    (net (code "59") (name "Net-(R3-Pad2)") (class "Default")
      (node (ref "R3") (pin "2") (pinfunction "2_2") (pintype "passive"))
      (node (ref "X1") (pin "D-") (pinfunction "D-_D-") (pintype "bidirectional"))
      (node (ref "Z1") (pin "2") (pinfunction "2_2") (pintype "passive"))
    )
    (net (code "60") (name "Net-(R4-Pad2)") (class "Default")
      (node (ref "R4") (pin "2") (pinfunction "2_2") (pintype "passive"))
      (node (ref "X1") (pin "D+") (pinfunction "D+_D+") (pintype "bidirectional"))
      (node (ref "Z2") (pin "2") (pinfunction "2_2") (pintype "passive"))
    )
    (net (code "61") (name "Net-(RX-A)") (class "Default")
      (node (ref "R20") (pin "1") (pinfunction "1_1") (pintype "passive"))
      (node (ref "RX") (pin "ANODE") (pinfunction "A_ANODE") (pintype "passive"))
    )
    (net (code "62") (name "Net-(TX-A)") (class "Default")
      (node (ref "R19") (pin "1") (pinfunction "1_1") (pintype "passive"))
      (node (ref "TX") (pin "ANODE") (pinfunction "A_ANODE") (pintype "passive"))
    )
    (net (code "63") (name "Net-(TX1-A)") (class "Default")
      (node (ref "R18") (pin "1") (pinfunction "1_1") (pintype "passive"))
      (node (ref "TX1") (pin "ANODE") (pinfunction "A_ANODE") (pintype "passive"))
    )
    (net (code "64") (name "unconnected-(7660-LV-Pad6)") (class "Default")
      (node (ref "7660") (pin "6") (pinfunction "LV_6") (pintype "passive"))
    )
    (net (code "65") (name "unconnected-(7660-NC-Pad1)") (class "Default")
      (node (ref "7660") (pin "1") (pinfunction "NC_1") (pintype "no_connect"))
    )
    (net (code "66") (name "unconnected-(AD5531-NC-Pad12)") (class "Default")
      (node (ref "AD5531") (pin "12") (pinfunction "NC_12") (pintype "passive"))
    )
    (net (code "67") (name "unconnected-(AD5531-RBEN*-Pad6)") (class "Default")
      (node (ref "AD5531") (pin "6") (pinfunction "RBEN*_6") (pintype "passive"))
    )
    (net (code "68") (name "unconnected-(AD8221-RG-Pad3)") (class "Default")
      (node (ref "AD8221") (pin "3") (pinfunction "RG_3") (pintype "passive"))
    )
    (net (code "69") (name "unconnected-(AD8221-RG_2-Pad2)") (class "Default")
      (node (ref "AD8221") (pin "2") (pinfunction "RG_2_2") (pintype "passive"))
    )
    (net (code "70") (name "unconnected-(ADR03BRZ-OPT-Pad3)") (class "Default")
      (node (ref "ADR03BRZ") (pin "3") (pinfunction "OPT_3") (pintype "output"))
    )
    (net (code "71") (name "unconnected-(ADR03BRZ-TRM-Pad5)") (class "Default")
      (node (ref "ADR03BRZ") (pin "5") (pinfunction "TRM_5") (pintype "input"))
    )
    (net (code "72") (name "unconnected-(ATMEGA32U4-AREF-Pad42)") (class "Default")
      (node (ref "ATMEGA32U4") (pin "42") (pinfunction "AREF_42") (pintype "bidirectional"))
    )
    (net (code "73") (name "unconnected-(ATMEGA32U4-PB7(OC0A{slash}OC1C{slash}RTS)-Pad12)") (class "Default")
      (node (ref "ATMEGA32U4") (pin "12") (pinfunction "PB7(OC0A/OC1C/RTS)_12") (pintype "bidirectional"))
    )
    (net (code "74") (name "unconnected-(ATMEGA32U4-PD6(T1{slash}OC4D{slash}ADC9)-Pad26)") (class "Default")
      (node (ref "ATMEGA32U4") (pin "26") (pinfunction "PD6(T1/OC4D/ADC9)_26") (pintype "bidirectional"))
    )
    (net (code "75") (name "unconnected-(ATMEGA32U4-PF7(ADC7(TDI)-Pad36)") (class "Default")
      (node (ref "ATMEGA32U4") (pin "36") (pinfunction "PF7(ADC7(TDI)_36") (pintype "bidirectional"))
    )
    (net (code "76") (name "unconnected-(RESET-1.2-Pad2)") (class "Default")
      (node (ref "RESET") (pin "2") (pinfunction "1.2_2") (pintype "passive"))
    )
    (net (code "77") (name "unconnected-(RESET-2.2-Pad4)") (class "Default")
      (node (ref "RESET") (pin "4") (pinfunction "2.2_4") (pintype "passive"))
    )
    (net (code "78") (name "unconnected-(RESET-SH-Pad5)") (class "Default")
      (node (ref "RESET") (pin "5") (pinfunction "SH_5") (pintype "passive"))
    )
    (net (code "79") (name "unconnected-(U$1-PadNC1)") (class "Default")
      (node (ref "U$1") (pin "NC1") (pinfunction "NC1_NC1") (pintype "bidirectional"))
    )
    (net (code "80") (name "unconnected-(U$1-PadNC2)") (class "Default")
      (node (ref "U$1") (pin "NC2") (pinfunction "NC2_NC2") (pintype "bidirectional"))
    )
  )
)
